# MM32_BLDC.net
KiCad netlist of a schematic drawn in Altium Designer
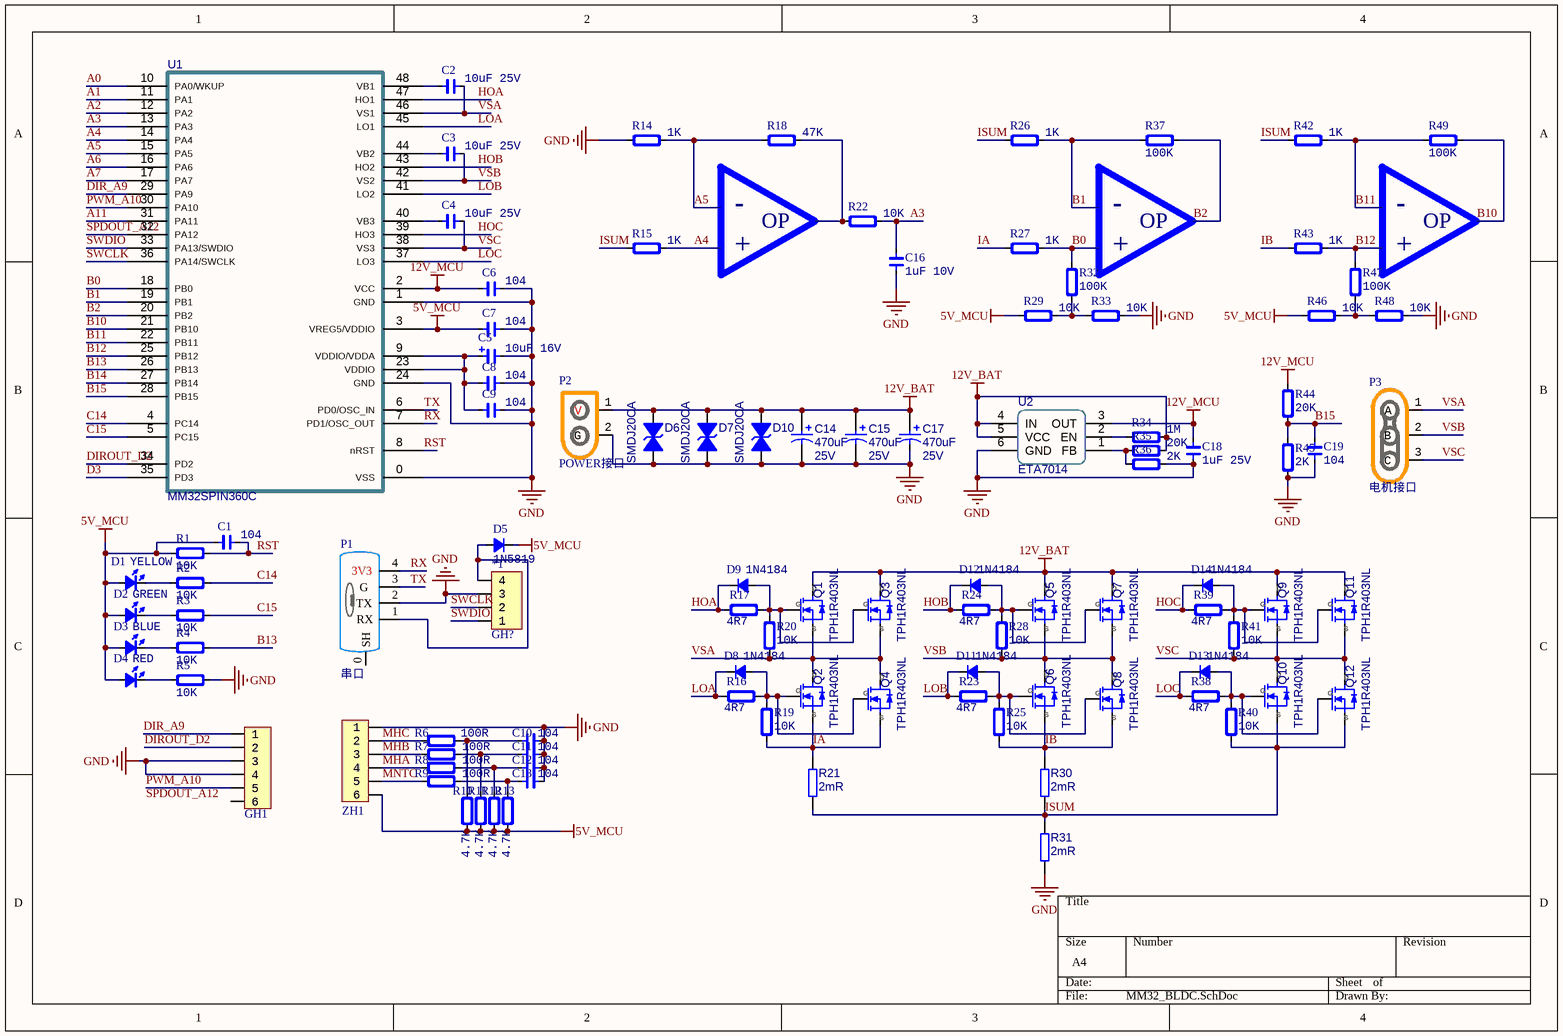
[diagram p0: MM32_BLDC.SchDoc]

(export (version "E")
  (design (tool "Eeschema 10.0.6"))
  (components
    (comp (ref "*1")
      (value "GH?")
      (footprint "MX 1.25-LS-4P")
      (description "MX")
      (libsource (lib "RM") (part "4P接口"))
    )
    (comp (ref "C1")
      (value "104")
      (footprint "CAP_0603")
      (description "Capacitor")
      (libsource (lib "") (part "Cap_0603_1"))
    )
    (comp (ref "C2")
      (value "10uF 25V")
      (footprint "CAP_0603")
      (description "Capacitor")
      (libsource (lib "") (part "Cap_0603_1"))
    )
    (comp (ref "C3")
      (value "10uF 25V")
      (footprint "CAP_0603")
      (description "Capacitor")
      (libsource (lib "") (part "Cap_0603_1"))
    )
    (comp (ref "C4")
      (value "10uF 25V")
      (footprint "CAP_0603")
      (description "Capacitor")
      (libsource (lib "") (part "Cap_0603_1"))
    )
    (comp (ref "C5")
      (value "10uF 16V")
      (footprint "CAP_TAN_A1206")
      (description "Capacitor Tantalum")
      (libsource (lib "KitSprout") (part "Cap_Tan_1206"))
    )
    (comp (ref "C6")
      (value "104")
      (footprint "CAP_0603")
      (description "Capacitor")
      (libsource (lib "") (part "Cap_0603_1"))
    )
    (comp (ref "C7")
      (value "104")
      (footprint "CAP_0603")
      (description "Capacitor")
      (libsource (lib "") (part "Cap_0603_1"))
    )
    (comp (ref "C8")
      (value "104")
      (footprint "CAP_0603")
      (description "Capacitor")
      (libsource (lib "") (part "Cap_0603_1"))
    )
    (comp (ref "C9")
      (value "104")
      (footprint "CAP_0603")
      (description "Capacitor")
      (libsource (lib "") (part "Cap_0603_1"))
    )
    (comp (ref "C10")
      (value "104")
      (footprint "CAP_0603")
      (description "Capacitor")
      (libsource (lib "KitSprout") (part "Cap_0603"))
    )
    (comp (ref "C11")
      (value "104")
      (footprint "CAP_0603")
      (description "Capacitor")
      (libsource (lib "KitSprout") (part "Cap_0603"))
    )
    (comp (ref "C12")
      (value "104")
      (footprint "CAP_0603")
      (description "Capacitor")
      (libsource (lib "KitSprout") (part "Cap_0603"))
    )
    (comp (ref "C13")
      (value "104")
      (footprint "CAP_0603")
      (description "Capacitor")
      (libsource (lib "KitSprout") (part "Cap_0603"))
    )
    (comp (ref "C14")
      (value "470uF")
      (footprint "CAPPR3.5-8X12")
      (description "Polarized Capacitor (Radial)")
      (fields
        (field (name "VOLTAGE") "25V")
        (field (name "Comment") "470uF 25V")
        (field (name "PUBLISHER") "Altium Limited")
      )
      (libsource (lib "灵动SPIN360C 无刷驱动V1.6 集成封装库") (part "Cap-Elect"))
    )
    (comp (ref "C15")
      (value "470uF")
      (footprint "CAPPR3.5-8X12")
      (description "Polarized Capacitor (Radial)")
      (fields
        (field (name "VOLTAGE") "25V")
        (field (name "Comment") "470uF 25V")
        (field (name "PUBLISHER") "Altium Limited")
      )
      (libsource (lib "灵动SPIN360C 无刷驱动V1.6 集成封装库") (part "Cap-Elect"))
    )
    (comp (ref "C16")
      (value "1uF 10V")
      (footprint "CAP_0603")
      (description "Capacitor")
      (libsource (lib "") (part "Cap_0603_2"))
    )
    (comp (ref "C17")
      (value "470uF")
      (footprint "CAPPR3.5-8X12")
      (description "Polarized Capacitor (Radial)")
      (fields
        (field (name "VOLTAGE") "25V")
        (field (name "Comment") "470uF 25V")
        (field (name "PUBLISHER") "Altium Limited")
      )
      (libsource (lib "灵动SPIN360C 无刷驱动V1.6 集成封装库") (part "Cap-Elect"))
    )
    (comp (ref "C18")
      (value "1uF 25V")
      (footprint "CAP_0603")
      (description "Capacitor")
      (libsource (lib "") (part "Cap_0603_2"))
    )
    (comp (ref "C19")
      (value "104")
      (footprint "CAP_0603")
      (description "Capacitor")
      (libsource (lib "") (part "Cap_0603_2"))
    )
    (comp (ref "D1")
      (value "YELLOW")
      (footprint "LED_0603_RED")
      (description "LED")
      (libsource (lib "KitSprout") (part "LED_0603"))
    )
    (comp (ref "D2")
      (value "GREEN")
      (footprint "LED_0603_RED")
      (description "LED")
      (libsource (lib "KitSprout") (part "LED_0603"))
    )
    (comp (ref "D3")
      (value "BLUE")
      (footprint "LED_0603_RED")
      (description "LED")
      (libsource (lib "KitSprout") (part "LED_0603"))
    )
    (comp (ref "D4")
      (value "RED")
      (footprint "LED_0603_RED")
      (description "LED")
      (libsource (lib "KitSprout") (part "LED_0603"))
    )
    (comp (ref "D5")
      (value "1N5819")
      (footprint "SOD-123")
      (description "Diode")
      (libsource (lib "KitSprout") (part "Diode_SOD123"))
    )
    (comp (ref "D6")
      (value "SMDJ20CA")
      (footprint "SMC[DO-214AB]")
      (description "TRANSIENT VOLTAGE  SUPPRESSOR DIODE")
      (fields (field (name "PUBLISHER") "Altium Limited"))
      (libsource (lib "灵动SPIN360C 无刷驱动V1.6 集成封装库") (part "Diode TVS Bi-Dir"))
    )
    (comp (ref "D7")
      (value "SMDJ20CA")
      (footprint "SMC[DO-214AB]")
      (description "TRANSIENT VOLTAGE  SUPPRESSOR DIODE")
      (fields (field (name "PUBLISHER") "Altium Limited"))
      (libsource (lib "灵动SPIN360C 无刷驱动V1.6 集成封装库") (part "Diode TVS Bi-Dir"))
    )
    (comp (ref "D8")
      (value "1N4184")
      (footprint "SOD-323")
      (description "Diode")
      (libsource (lib "KitSprout") (part "Diode_SOD323"))
    )
    (comp (ref "D9")
      (value "1N4184")
      (footprint "SOD-323")
      (description "Diode")
      (libsource (lib "KitSprout") (part "Diode_SOD323"))
    )
    (comp (ref "D10")
      (value "SMDJ20CA")
      (footprint "SMC[DO-214AB]")
      (description "TRANSIENT VOLTAGE  SUPPRESSOR DIODE")
      (fields (field (name "PUBLISHER") "Altium Limited"))
      (libsource (lib "灵动SPIN360C 无刷驱动V1.6 集成封装库") (part "Diode TVS Bi-Dir"))
    )
    (comp (ref "D11")
      (value "1N4184")
      (footprint "SOD-323")
      (description "Diode")
      (libsource (lib "KitSprout") (part "Diode_SOD323"))
    )
    (comp (ref "D12")
      (value "1N4184")
      (footprint "SOD-323")
      (description "Diode")
      (libsource (lib "KitSprout") (part "Diode_SOD323"))
    )
    (comp (ref "D13")
      (value "1N4184")
      (footprint "SOD-323")
      (description "Diode")
      (libsource (lib "KitSprout") (part "Diode_SOD323"))
    )
    (comp (ref "D14")
      (value "1N4184")
      (footprint "SOD-323")
      (description "Diode")
      (libsource (lib "KitSprout") (part "Diode_SOD323"))
    )
    (comp (ref "GH1")
      (value "HDR1x6")
      (footprint "MX 1.25-WS-4P")
      (description "Header")
      (libsource (lib "MM32_FOC") (part "HDR1x6_2.54"))
    )
    (comp (ref "P1")
      (value "串口")
      (footprint "GH1.25-LS-4P")
      (description "MX")
      (libsource (lib "RM") (part "串口"))
    )
    (comp (ref "P2")
      (value "POWER接口")
      (footprint "XT30UPB-M")
      (description "POWER")
      (libsource (lib "RM") (part "POWER接口"))
    )
    (comp (ref "P3") (value "电机接口") (footprint "AMASS-MR30-M") (libsource (lib "RM") (part "电机接口")))
    (comp (ref "Q1")
      (value "TPH1R403NL")
      (footprint "DFN5x6")
      (description "东芝 N沟 MOS")
      (libsource (lib "灵动SPIN360C 无刷驱动V1.6 集成封装库") (part "TPH1R403NL"))
    )
    (comp (ref "Q2")
      (value "TPH1R403NL")
      (footprint "DFN5x6")
      (description "东芝 N沟 MOS")
      (libsource (lib "灵动SPIN360C 无刷驱动V1.6 集成封装库") (part "TPH1R403NL"))
    )
    (comp (ref "Q3")
      (value "TPH1R403NL")
      (footprint "DFN5x6")
      (description "东芝 N沟 MOS")
      (libsource (lib "灵动SPIN360C 无刷驱动V1.6 集成封装库") (part "TPH1R403NL"))
    )
    (comp (ref "Q4")
      (value "TPH1R403NL")
      (footprint "DFN5x6")
      (description "东芝 N沟 MOS")
      (libsource (lib "灵动SPIN360C 无刷驱动V1.6 集成封装库") (part "TPH1R403NL"))
    )
    (comp (ref "Q5")
      (value "TPH1R403NL")
      (footprint "DFN5x6")
      (description "东芝 N沟 MOS")
      (libsource (lib "灵动SPIN360C 无刷驱动V1.6 集成封装库") (part "TPH1R403NL"))
    )
    (comp (ref "Q6")
      (value "TPH1R403NL")
      (footprint "DFN5x6")
      (description "东芝 N沟 MOS")
      (libsource (lib "灵动SPIN360C 无刷驱动V1.6 集成封装库") (part "TPH1R403NL"))
    )
    (comp (ref "Q7")
      (value "TPH1R403NL")
      (footprint "DFN5x6")
      (description "东芝 N沟 MOS")
      (libsource (lib "灵动SPIN360C 无刷驱动V1.6 集成封装库") (part "TPH1R403NL"))
    )
    (comp (ref "Q8")
      (value "TPH1R403NL")
      (footprint "DFN5x6")
      (description "东芝 N沟 MOS")
      (libsource (lib "灵动SPIN360C 无刷驱动V1.6 集成封装库") (part "TPH1R403NL"))
    )
    (comp (ref "Q9")
      (value "TPH1R403NL")
      (footprint "DFN5x6")
      (description "东芝 N沟 MOS")
      (libsource (lib "灵动SPIN360C 无刷驱动V1.6 集成封装库") (part "TPH1R403NL"))
    )
    (comp (ref "Q10")
      (value "TPH1R403NL")
      (footprint "DFN5x6")
      (description "东芝 N沟 MOS")
      (libsource (lib "灵动SPIN360C 无刷驱动V1.6 集成封装库") (part "TPH1R403NL"))
    )
    (comp (ref "Q11")
      (value "TPH1R403NL")
      (footprint "DFN5x6")
      (description "东芝 N沟 MOS")
      (libsource (lib "灵动SPIN360C 无刷驱动V1.6 集成封装库") (part "TPH1R403NL"))
    )
    (comp (ref "Q12")
      (value "TPH1R403NL")
      (footprint "DFN5x6")
      (description "东芝 N沟 MOS")
      (libsource (lib "灵动SPIN360C 无刷驱动V1.6 集成封装库") (part "TPH1R403NL"))
    )
    (comp (ref "R1")
      (value "10K")
      (footprint "RES_0603")
      (description "Resistor")
      (libsource (lib "KitSprout") (part "Res_0603"))
    )
    (comp (ref "R2")
      (value "10K")
      (footprint "RES_0603")
      (description "Resistor")
      (libsource (lib "KitSprout") (part "Res_0603"))
    )
    (comp (ref "R3")
      (value "10K")
      (footprint "RES_0603")
      (description "Resistor")
      (libsource (lib "KitSprout") (part "Res_0603"))
    )
    (comp (ref "R4")
      (value "10K")
      (footprint "RES_0603")
      (description "Resistor")
      (libsource (lib "KitSprout") (part "Res_0603"))
    )
    (comp (ref "R5")
      (value "10K")
      (footprint "RES_0603")
      (description "Resistor")
      (libsource (lib "KitSprout") (part "Res_0603"))
    )
    (comp (ref "R6")
      (value "100R")
      (footprint "RES_0603")
      (description "Resistor")
      (libsource (lib "KitSprout") (part "Res_0603"))
    )
    (comp (ref "R7")
      (value "100R")
      (footprint "RES_0603")
      (description "Resistor")
      (libsource (lib "KitSprout") (part "Res_0603"))
    )
    (comp (ref "R8")
      (value "100R")
      (footprint "RES_0603")
      (description "Resistor")
      (libsource (lib "KitSprout") (part "Res_0603"))
    )
    (comp (ref "R9")
      (value "100R")
      (footprint "RES_0603")
      (description "Resistor")
      (libsource (lib "KitSprout") (part "Res_0603"))
    )
    (comp (ref "R10")
      (value "4.7K")
      (footprint "RES_0603")
      (description "Resistor")
      (libsource (lib "KitSprout") (part "Res_0603"))
    )
    (comp (ref "R11")
      (value "4.7K")
      (footprint "RES_0603")
      (description "Resistor")
      (libsource (lib "KitSprout") (part "Res_0603"))
    )
    (comp (ref "R12")
      (value "4.7K")
      (footprint "RES_0603")
      (description "Resistor")
      (libsource (lib "KitSprout") (part "Res_0603"))
    )
    (comp (ref "R13")
      (value "4.7K")
      (footprint "RES_0603")
      (description "Resistor")
      (libsource (lib "KitSprout") (part "Res_0603"))
    )
    (comp (ref "R14")
      (value "1K")
      (footprint "RES_0603")
      (description "Resistor")
      (libsource (lib "KitSprout") (part "Res_0603"))
    )
    (comp (ref "R15")
      (value "1K")
      (footprint "RES_0603")
      (description "Resistor")
      (libsource (lib "KitSprout") (part "Res_0603"))
    )
    (comp (ref "R16")
      (value "4R7")
      (footprint "RES_0603")
      (description "Resistor")
      (libsource (lib "KitSprout") (part "Res_0603"))
    )
    (comp (ref "R17")
      (value "4R7")
      (footprint "RES_0603")
      (description "Resistor")
      (libsource (lib "KitSprout") (part "Res_0603"))
    )
    (comp (ref "R18")
      (value "47K")
      (footprint "RES_0603")
      (description "Resistor")
      (libsource (lib "KitSprout") (part "Res_0603"))
    )
    (comp (ref "R19")
      (value "10K")
      (footprint "RES_0603")
      (description "Resistor")
      (libsource (lib "KitSprout") (part "Res_0603"))
    )
    (comp (ref "R20")
      (value "10K")
      (footprint "RES_0603")
      (description "Resistor")
      (libsource (lib "KitSprout") (part "Res_0603"))
    )
    (comp (ref "R21")
      (value "2mR")
      (footprint "RESC6332[2512]S")
      (description "贴片电阻")
      (fields (field (name "TOLERANCE") "±1%") (field (name "Comment") "2mR ±1%"))
      (libsource (lib "灵动SPIN360C 无刷驱动V1.6 集成封装库") (part "Res-Chip_11"))
    )
    (comp (ref "R22")
      (value "10K")
      (footprint "RES_0603")
      (description "Resistor")
      (libsource (lib "KitSprout") (part "Res_0603"))
    )
    (comp (ref "R23")
      (value "4R7")
      (footprint "RES_0603")
      (description "Resistor")
      (libsource (lib "KitSprout") (part "Res_0603"))
    )
    (comp (ref "R24")
      (value "4R7")
      (footprint "RES_0603")
      (description "Resistor")
      (libsource (lib "KitSprout") (part "Res_0603"))
    )
    (comp (ref "R25")
      (value "10K")
      (footprint "RES_0603")
      (description "Resistor")
      (libsource (lib "KitSprout") (part "Res_0603"))
    )
    (comp (ref "R26")
      (value "1K")
      (footprint "RES_0603")
      (description "Resistor")
      (libsource (lib "KitSprout") (part "Res_0603"))
    )
    (comp (ref "R27")
      (value "1K")
      (footprint "RES_0603")
      (description "Resistor")
      (libsource (lib "KitSprout") (part "Res_0603"))
    )
    (comp (ref "R28")
      (value "10K")
      (footprint "RES_0603")
      (description "Resistor")
      (libsource (lib "KitSprout") (part "Res_0603"))
    )
    (comp (ref "R29")
      (value "10K")
      (footprint "RES_0603")
      (description "Resistor")
      (libsource (lib "KitSprout") (part "Res_0603"))
    )
    (comp (ref "R30")
      (value "2mR")
      (footprint "RESC6332[2512]S")
      (description "贴片电阻")
      (fields (field (name "TOLERANCE") "±1%") (field (name "Comment") "2mR ±1%"))
      (libsource (lib "灵动SPIN360C 无刷驱动V1.6 集成封装库") (part "Res-Chip_11"))
    )
    (comp (ref "R31")
      (value "2mR")
      (footprint "RESC6332[2512]S")
      (description "贴片电阻")
      (fields (field (name "TOLERANCE") "±1%") (field (name "Comment") "2mR ±1%"))
      (libsource (lib "灵动SPIN360C 无刷驱动V1.6 集成封装库") (part "Res-Chip_11"))
    )
    (comp (ref "R32")
      (value "100K")
      (footprint "RES_0603")
      (description "Resistor")
      (libsource (lib "KitSprout") (part "Res_0603"))
    )
    (comp (ref "R33")
      (value "10K")
      (footprint "RES_0603")
      (description "Resistor")
      (libsource (lib "KitSprout") (part "Res_0603"))
    )
    (comp (ref "R34")
      (value "1M")
      (footprint "RES_0603")
      (description "Resistor")
      (libsource (lib "KitSprout") (part "Res_0603"))
    )
    (comp (ref "R35")
      (value "20K")
      (footprint "RES_0603")
      (description "Resistor")
      (libsource (lib "KitSprout") (part "Res_0603"))
    )
    (comp (ref "R36")
      (value "2K")
      (footprint "RES_0603")
      (description "Resistor")
      (libsource (lib "KitSprout") (part "Res_0603"))
    )
    (comp (ref "R37")
      (value "100K")
      (footprint "RES_0603")
      (description "Resistor")
      (libsource (lib "KitSprout") (part "Res_0603"))
    )
    (comp (ref "R38")
      (value "4R7")
      (footprint "RES_0603")
      (description "Resistor")
      (libsource (lib "KitSprout") (part "Res_0603"))
    )
    (comp (ref "R39")
      (value "4R7")
      (footprint "RES_0603")
      (description "Resistor")
      (libsource (lib "KitSprout") (part "Res_0603"))
    )
    (comp (ref "R40")
      (value "10K")
      (footprint "RES_0603")
      (description "Resistor")
      (libsource (lib "KitSprout") (part "Res_0603"))
    )
    (comp (ref "R41")
      (value "10K")
      (footprint "RES_0603")
      (description "Resistor")
      (libsource (lib "KitSprout") (part "Res_0603"))
    )
    (comp (ref "R42")
      (value "1K")
      (footprint "RES_0603")
      (description "Resistor")
      (libsource (lib "KitSprout") (part "Res_0603"))
    )
    (comp (ref "R43")
      (value "1K")
      (footprint "RES_0603")
      (description "Resistor")
      (libsource (lib "KitSprout") (part "Res_0603"))
    )
    (comp (ref "R44")
      (value "20K")
      (footprint "RES_0603")
      (description "Resistor")
      (libsource (lib "KitSprout") (part "Res_0603"))
    )
    (comp (ref "R45")
      (value "2K")
      (footprint "RES_0603")
      (description "Resistor")
      (libsource (lib "KitSprout") (part "Res_0603"))
    )
    (comp (ref "R46")
      (value "10K")
      (footprint "RES_0603")
      (description "Resistor")
      (libsource (lib "KitSprout") (part "Res_0603"))
    )
    (comp (ref "R47")
      (value "100K")
      (footprint "RES_0603")
      (description "Resistor")
      (libsource (lib "KitSprout") (part "Res_0603"))
    )
    (comp (ref "R48")
      (value "10K")
      (footprint "RES_0603")
      (description "Resistor")
      (libsource (lib "KitSprout") (part "Res_0603"))
    )
    (comp (ref "R49")
      (value "100K")
      (footprint "RES_0603")
      (description "Resistor")
      (libsource (lib "KitSprout") (part "Res_0603"))
    )
    (comp (ref "U1")
      (value "MM32SPIN360C")
      (footprint "QFN48-6x6")
      (fields (field (name "PUBLISHER") "Altium Limited"))
      (libsource (lib "灵动SPIN360C 无刷驱动V1.6 集成封装库") (part "MM32SPIN360C"))
    )
    (comp (ref "U2")
      (value "ETA7014")
      (footprint "SOT-23-6")
      (description "ETA7014 OVP芯片")
      (libsource (lib "灵动SPIN360C 无刷驱动V1.6 集成封装库") (part "ETA7014"))
    )
    (comp (ref "ZH1")
      (value "MX1.25_6P")
      (footprint "ZH1.5-WF-6P")
      (description "MX")
      (libsource (lib "KitSprout") (part "MX1.25_6P"))
    )
  )
  (nets
    (net (code "1") (name "/A0") (class "Default")
      (node (ref "U1") (pin "10") (pinfunction "PA0/WKUP_10") (pintype "passive"))
    )
    (net (code "2") (name "/A1") (class "Default")
      (node (ref "U1") (pin "11") (pinfunction "PA1_11") (pintype "passive"))
    )
    (net (code "3") (name "/A2") (class "Default")
      (node (ref "U1") (pin "12") (pinfunction "PA2_12") (pintype "passive"))
    )
    (net (code "4") (name "/A3") (class "Default")
      (node (ref "C16") (pin "2") (pinfunction "2_2") (pintype "passive"))
      (node (ref "R22") (pin "1") (pinfunction "1_1") (pintype "passive"))
      (node (ref "U1") (pin "13") (pinfunction "PA3_13") (pintype "passive"))
    )
    (net (code "5") (name "/A4") (class "Default")
      (node (ref "R15") (pin "1") (pinfunction "1_1") (pintype "passive"))
      (node (ref "U1") (pin "14") (pinfunction "PA4_14") (pintype "passive"))
    )
    (net (code "6") (name "/A5") (class "Default")
      (node (ref "R14") (pin "1") (pinfunction "1_1") (pintype "passive"))
      (node (ref "R18") (pin "2") (pinfunction "2_2") (pintype "passive"))
      (node (ref "U1") (pin "15") (pinfunction "PA5_15") (pintype "passive"))
    )
    (net (code "7") (name "/A6") (class "Default")
      (node (ref "U1") (pin "16") (pinfunction "PA6_16") (pintype "passive"))
    )
    (net (code "8") (name "/A7") (class "Default")
      (node (ref "U1") (pin "17") (pinfunction "PA7_17") (pintype "passive"))
    )
    (net (code "9") (name "/A11") (class "Default")
      (node (ref "U1") (pin "31") (pinfunction "PA11_31") (pintype "passive"))
    )
    (net (code "10") (name "/B0") (class "Default")
      (node (ref "R27") (pin "1") (pinfunction "1_1") (pintype "passive"))
      (node (ref "R32") (pin "1") (pinfunction "1_1") (pintype "passive"))
      (node (ref "U1") (pin "18") (pinfunction "PB0_18") (pintype "passive"))
    )
    (net (code "11") (name "/B1") (class "Default")
      (node (ref "R26") (pin "1") (pinfunction "1_1") (pintype "passive"))
      (node (ref "R37") (pin "1") (pinfunction "1_1") (pintype "passive"))
      (node (ref "U1") (pin "19") (pinfunction "PB1_19") (pintype "passive"))
    )
    (net (code "12") (name "/B2") (class "Default")
      (node (ref "R37") (pin "2") (pinfunction "2_2") (pintype "passive"))
      (node (ref "U1") (pin "20") (pinfunction "PB2_20") (pintype "passive"))
    )
    (net (code "13") (name "/B10") (class "Default")
      (node (ref "R49") (pin "2") (pinfunction "2_2") (pintype "passive"))
      (node (ref "U1") (pin "21") (pinfunction "PB10_21") (pintype "passive"))
    )
    (net (code "14") (name "/B11") (class "Default")
      (node (ref "R42") (pin "1") (pinfunction "1_1") (pintype "passive"))
      (node (ref "R49") (pin "1") (pinfunction "1_1") (pintype "passive"))
      (node (ref "U1") (pin "22") (pinfunction "PB11_22") (pintype "passive"))
    )
    (net (code "15") (name "/B12") (class "Default")
      (node (ref "R43") (pin "1") (pinfunction "1_1") (pintype "passive"))
      (node (ref "R47") (pin "1") (pinfunction "1_1") (pintype "passive"))
      (node (ref "U1") (pin "25") (pinfunction "PB12_25") (pintype "passive"))
    )
    (net (code "16") (name "/B13") (class "Default")
      (node (ref "R4") (pin "2") (pinfunction "2_2") (pintype "passive"))
      (node (ref "U1") (pin "26") (pinfunction "PB13_26") (pintype "passive"))
    )
    (net (code "17") (name "/B14") (class "Default")
      (node (ref "U1") (pin "27") (pinfunction "PB14_27") (pintype "passive"))
    )
    (net (code "18") (name "/B15") (class "Default")
      (node (ref "C19") (pin "2") (pinfunction "2_2") (pintype "passive"))
      (node (ref "R44") (pin "2") (pinfunction "2_2") (pintype "passive"))
      (node (ref "R45") (pin "1") (pinfunction "1_1") (pintype "passive"))
      (node (ref "U1") (pin "28") (pinfunction "PB15_28") (pintype "passive"))
    )
    (net (code "19") (name "/C14") (class "Default")
      (node (ref "R2") (pin "2") (pinfunction "2_2") (pintype "passive"))
      (node (ref "U1") (pin "4") (pinfunction "PC14_4") (pintype "passive"))
    )
    (net (code "20") (name "/C15") (class "Default")
      (node (ref "R3") (pin "2") (pinfunction "2_2") (pintype "passive"))
      (node (ref "U1") (pin "5") (pinfunction "PC15_5") (pintype "passive"))
    )
    (net (code "21") (name "/D3") (class "Default")
      (node (ref "U1") (pin "35") (pinfunction "PD3_35") (pintype "passive"))
    )
    (net (code "22") (name "/DIROUT_D2") (class "Default")
      (node (ref "GH1") (pin "2") (pinfunction "2_2") (pintype "passive"))
      (node (ref "U1") (pin "34") (pinfunction "PD2_34") (pintype "passive"))
    )
    (net (code "23") (name "/DIR_A9") (class "Default")
      (node (ref "GH1") (pin "1") (pinfunction "1_1") (pintype "passive"))
      (node (ref "U1") (pin "29") (pinfunction "PA9_29") (pintype "passive"))
    )
    (net (code "24") (name "/HOA") (class "Default")
      (node (ref "D9") (pin "2") (pinfunction "K_2") (pintype "passive"))
      (node (ref "R17") (pin "2") (pinfunction "2_2") (pintype "passive"))
      (node (ref "U1") (pin "47") (pinfunction "HO1_47") (pintype "passive"))
    )
    (net (code "25") (name "/HOB") (class "Default")
      (node (ref "D12") (pin "2") (pinfunction "K_2") (pintype "passive"))
      (node (ref "R24") (pin "2") (pinfunction "2_2") (pintype "passive"))
      (node (ref "U1") (pin "43") (pinfunction "HO2_43") (pintype "passive"))
    )
    (net (code "26") (name "/HOC") (class "Default")
      (node (ref "D14") (pin "2") (pinfunction "K_2") (pintype "passive"))
      (node (ref "R39") (pin "2") (pinfunction "2_2") (pintype "passive"))
      (node (ref "U1") (pin "39") (pinfunction "HO3_39") (pintype "passive"))
    )
    (net (code "27") (name "/IA") (class "Default")
      (node (ref "Q2") (pin "3") (pinfunction "S_3") (pintype "passive"))
      (node (ref "Q4") (pin "3") (pinfunction "S_3") (pintype "passive"))
      (node (ref "R19") (pin "2") (pinfunction "2_2") (pintype "passive"))
      (node (ref "R21") (pin "2") (pinfunction "2_2") (pintype "passive"))
      (node (ref "R27") (pin "2") (pinfunction "2_2") (pintype "passive"))
    )
    (net (code "28") (name "/IB") (class "Default")
      (node (ref "Q6") (pin "3") (pinfunction "S_3") (pintype "passive"))
      (node (ref "Q8") (pin "3") (pinfunction "S_3") (pintype "passive"))
      (node (ref "R25") (pin "2") (pinfunction "2_2") (pintype "passive"))
      (node (ref "R30") (pin "2") (pinfunction "2_2") (pintype "passive"))
      (node (ref "R43") (pin "2") (pinfunction "2_2") (pintype "passive"))
    )
    (net (code "29") (name "/ISUM") (class "Default")
      (node (ref "Q10") (pin "3") (pinfunction "S_3") (pintype "passive"))
      (node (ref "Q12") (pin "3") (pinfunction "S_3") (pintype "passive"))
      (node (ref "R15") (pin "2") (pinfunction "2_2") (pintype "passive"))
      (node (ref "R21") (pin "1") (pinfunction "1_1") (pintype "passive"))
      (node (ref "R26") (pin "2") (pinfunction "2_2") (pintype "passive"))
      (node (ref "R30") (pin "1") (pinfunction "1_1") (pintype "passive"))
      (node (ref "R31") (pin "2") (pinfunction "2_2") (pintype "passive"))
      (node (ref "R40") (pin "2") (pinfunction "2_2") (pintype "passive"))
      (node (ref "R42") (pin "2") (pinfunction "2_2") (pintype "passive"))
    )
    (net (code "30") (name "/LOA") (class "Default")
      (node (ref "D8") (pin "2") (pinfunction "K_2") (pintype "passive"))
      (node (ref "R16") (pin "2") (pinfunction "2_2") (pintype "passive"))
      (node (ref "U1") (pin "45") (pinfunction "LO1_45") (pintype "passive"))
    )
    (net (code "31") (name "/LOB") (class "Default")
      (node (ref "D11") (pin "2") (pinfunction "K_2") (pintype "passive"))
      (node (ref "R23") (pin "2") (pinfunction "2_2") (pintype "passive"))
      (node (ref "U1") (pin "41") (pinfunction "LO2_41") (pintype "passive"))
    )
    (net (code "32") (name "/LOC") (class "Default")
      (node (ref "D13") (pin "2") (pinfunction "K_2") (pintype "passive"))
      (node (ref "R38") (pin "2") (pinfunction "2_2") (pintype "passive"))
      (node (ref "U1") (pin "37") (pinfunction "LO3_37") (pintype "passive"))
    )
    (net (code "33") (name "/MHA") (class "Default")
      (node (ref "R8") (pin "1") (pinfunction "1_1") (pintype "passive"))
      (node (ref "ZH1") (pin "4") (pinfunction "4_4") (pintype "passive"))
    )
    (net (code "34") (name "/MHB") (class "Default")
      (node (ref "R7") (pin "1") (pinfunction "1_1") (pintype "passive"))
      (node (ref "ZH1") (pin "3") (pinfunction "3_3") (pintype "passive"))
    )
    (net (code "35") (name "/MHC") (class "Default")
      (node (ref "R6") (pin "1") (pinfunction "1_1") (pintype "passive"))
      (node (ref "ZH1") (pin "2") (pinfunction "2_2") (pintype "passive"))
    )
    (net (code "36") (name "/MNTC") (class "Default")
      (node (ref "R9") (pin "1") (pinfunction "1_1") (pintype "passive"))
      (node (ref "ZH1") (pin "5") (pinfunction "5_5") (pintype "passive"))
    )
    (net (code "37") (name "/PWM_A10") (class "Default")
      (node (ref "GH1") (pin "5") (pinfunction "5_5") (pintype "passive"))
      (node (ref "U1") (pin "30") (pinfunction "PA10_30") (pintype "passive"))
    )
    (net (code "38") (name "/RST") (class "Default")
      (node (ref "C1") (pin "2") (pinfunction "2_2") (pintype "passive"))
      (node (ref "R1") (pin "2") (pinfunction "2_2") (pintype "passive"))
      (node (ref "U1") (pin "8") (pinfunction "nRST_8") (pintype "passive"))
    )
    (net (code "39") (name "/RX") (class "Default")
      (node (ref "P1") (pin "4") (pinfunction "3V3_4") (pintype "passive"))
      (node (ref "U1") (pin "7") (pinfunction "PD1/OSC_OUT_7") (pintype "passive"))
    )
    (net (code "40") (name "/SPDOUT_A12") (class "Default")
      (node (ref "U1") (pin "32") (pinfunction "PA12_32") (pintype "passive"))
    )
    (net (code "41") (name "/SWCLK") (class "Default")
      (node (ref "*1") (pin "2") (pinfunction "2_2") (pintype "passive"))
      (node (ref "U1") (pin "36") (pinfunction "PA14/SWCLK_36") (pintype "passive"))
    )
    (net (code "42") (name "/SWDIO") (class "Default")
      (node (ref "*1") (pin "1") (pinfunction "1_1") (pintype "passive"))
      (node (ref "U1") (pin "33") (pinfunction "PA13/SWDIO_33") (pintype "passive"))
    )
    (net (code "43") (name "/TX") (class "Default")
      (node (ref "P1") (pin "3") (pinfunction "G_3") (pintype "passive"))
      (node (ref "U1") (pin "6") (pinfunction "PD0/OSC_IN_6") (pintype "passive"))
    )
    (net (code "44") (name "/VSA") (class "Default")
      (node (ref "C2") (pin "2") (pinfunction "2_2") (pintype "passive"))
      (node (ref "P3") (pin "1") (pinfunction "A_1") (pintype "passive"))
      (node (ref "Q1") (pin "3") (pinfunction "S_3") (pintype "passive"))
      (node (ref "Q2") (pin "1") (pinfunction "D_1") (pintype "passive"))
      (node (ref "Q3") (pin "3") (pinfunction "S_3") (pintype "passive"))
      (node (ref "Q4") (pin "1") (pinfunction "D_1") (pintype "passive"))
      (node (ref "R20") (pin "2") (pinfunction "2_2") (pintype "passive"))
      (node (ref "U1") (pin "46") (pinfunction "VS1_46") (pintype "passive"))
    )
    (net (code "45") (name "/VSB") (class "Default")
      (node (ref "C3") (pin "2") (pinfunction "2_2") (pintype "passive"))
      (node (ref "P3") (pin "2") (pinfunction "B_2") (pintype "passive"))
      (node (ref "Q5") (pin "3") (pinfunction "S_3") (pintype "passive"))
      (node (ref "Q6") (pin "1") (pinfunction "D_1") (pintype "passive"))
      (node (ref "Q7") (pin "3") (pinfunction "S_3") (pintype "passive"))
      (node (ref "Q8") (pin "1") (pinfunction "D_1") (pintype "passive"))
      (node (ref "R28") (pin "2") (pinfunction "2_2") (pintype "passive"))
      (node (ref "U1") (pin "42") (pinfunction "VS2_42") (pintype "passive"))
    )
    (net (code "46") (name "/VSC") (class "Default")
      (node (ref "C4") (pin "2") (pinfunction "2_2") (pintype "passive"))
      (node (ref "P3") (pin "3") (pinfunction "C_3") (pintype "passive"))
      (node (ref "Q10") (pin "1") (pinfunction "D_1") (pintype "passive"))
      (node (ref "Q11") (pin "3") (pinfunction "S_3") (pintype "passive"))
      (node (ref "Q12") (pin "1") (pinfunction "D_1") (pintype "passive"))
      (node (ref "Q9") (pin "3") (pinfunction "S_3") (pintype "passive"))
      (node (ref "R41") (pin "2") (pinfunction "2_2") (pintype "passive"))
      (node (ref "U1") (pin "38") (pinfunction "VS3_38") (pintype "passive"))
    )
    (net (code "47") (name "5V_MCU") (class "Default")
      (node (ref "C1") (pin "1") (pinfunction "1_1") (pintype "passive"))
      (node (ref "C7") (pin "1") (pinfunction "1_1") (pintype "passive"))
      (node (ref "D1") (pin "1") (pinfunction "A_1") (pintype "passive"))
      (node (ref "D2") (pin "1") (pinfunction "A_1") (pintype "passive"))
      (node (ref "D3") (pin "1") (pinfunction "A_1") (pintype "passive"))
      (node (ref "D4") (pin "1") (pinfunction "A_1") (pintype "passive"))
      (node (ref "D5") (pin "2") (pinfunction "K_2") (pintype "passive"))
      (node (ref "R1") (pin "1") (pinfunction "1_1") (pintype "passive"))
      (node (ref "R10") (pin "2") (pinfunction "2_2") (pintype "passive"))
      (node (ref "R11") (pin "2") (pinfunction "2_2") (pintype "passive"))
      (node (ref "R12") (pin "2") (pinfunction "2_2") (pintype "passive"))
      (node (ref "R13") (pin "2") (pinfunction "2_2") (pintype "passive"))
      (node (ref "R29") (pin "2") (pinfunction "2_2") (pintype "passive"))
      (node (ref "R46") (pin "2") (pinfunction "2_2") (pintype "passive"))
      (node (ref "U1") (pin "3") (pinfunction "VREG5/VDDIO_3") (pintype "passive"))
      (node (ref "ZH1") (pin "6") (pinfunction "6_6") (pintype "passive"))
    )
    (net (code "48") (name "12V_BAT") (class "Default")
      (node (ref "C14") (pin "1") (pinfunction "1_1") (pintype "passive"))
      (node (ref "C15") (pin "1") (pinfunction "1_1") (pintype "passive"))
      (node (ref "C17") (pin "1") (pinfunction "1_1") (pintype "passive"))
      (node (ref "D10") (pin "K") (pinfunction "K_K") (pintype "passive"))
      (node (ref "D6") (pin "K") (pinfunction "K_K") (pintype "passive"))
      (node (ref "D7") (pin "K") (pinfunction "K_K") (pintype "passive"))
      (node (ref "P2") (pin "1") (pinfunction "V_1") (pintype "passive"))
      (node (ref "Q1") (pin "1") (pinfunction "D_1") (pintype "passive"))
      (node (ref "Q11") (pin "1") (pinfunction "D_1") (pintype "passive"))
      (node (ref "Q3") (pin "1") (pinfunction "D_1") (pintype "passive"))
      (node (ref "Q5") (pin "1") (pinfunction "D_1") (pintype "passive"))
      (node (ref "Q7") (pin "1") (pinfunction "D_1") (pintype "passive"))
      (node (ref "Q9") (pin "1") (pinfunction "D_1") (pintype "passive"))
      (node (ref "R34") (pin "1") (pinfunction "1_1") (pintype "passive"))
      (node (ref "R35") (pin "1") (pinfunction "1_1") (pintype "passive"))
      (node (ref "U2") (pin "4") (pinfunction "IN_4") (pintype "passive"))
      (node (ref "U2") (pin "5") (pinfunction "VCC_5") (pintype "passive"))
    )
    (net (code "49") (name "12V_MCU") (class "Default")
      (node (ref "C18") (pin "2") (pinfunction "2_2") (pintype "passive"))
      (node (ref "C6") (pin "1") (pinfunction "1_1") (pintype "passive"))
      (node (ref "R44") (pin "1") (pinfunction "1_1") (pintype "passive"))
      (node (ref "U1") (pin "2") (pinfunction "VCC_2") (pintype "passive"))
      (node (ref "U2") (pin "3") (pinfunction "OUT_3") (pintype "passive"))
    )
    (net (code "50") (name "GND") (class "Default")
      (node (ref "*1") (pin "3") (pinfunction "3_3") (pintype "passive"))
      (node (ref "C10") (pin "1") (pinfunction "1_1") (pintype "passive"))
      (node (ref "C11") (pin "1") (pinfunction "1_1") (pintype "passive"))
      (node (ref "C12") (pin "1") (pinfunction "1_1") (pintype "passive"))
      (node (ref "C13") (pin "1") (pinfunction "1_1") (pintype "passive"))
      (node (ref "C14") (pin "2") (pinfunction "2_2") (pintype "passive"))
      (node (ref "C15") (pin "2") (pinfunction "2_2") (pintype "passive"))
      (node (ref "C16") (pin "1") (pinfunction "1_1") (pintype "passive"))
      (node (ref "C17") (pin "2") (pinfunction "2_2") (pintype "passive"))
      (node (ref "C18") (pin "1") (pinfunction "1_1") (pintype "passive"))
      (node (ref "C19") (pin "1") (pinfunction "1_1") (pintype "passive"))
      (node (ref "C5") (pin "2") (pinfunction "2_2") (pintype "passive"))
      (node (ref "C6") (pin "2") (pinfunction "2_2") (pintype "passive"))
      (node (ref "C7") (pin "2") (pinfunction "2_2") (pintype "passive"))
      (node (ref "C8") (pin "2") (pinfunction "2_2") (pintype "passive"))
      (node (ref "C9") (pin "2") (pinfunction "2_2") (pintype "passive"))
      (node (ref "D10") (pin "A") (pinfunction "A_A") (pintype "passive"))
      (node (ref "D6") (pin "A") (pinfunction "A_A") (pintype "passive"))
      (node (ref "D7") (pin "A") (pinfunction "A_A") (pintype "passive"))
      (node (ref "GH1") (pin "3") (pinfunction "3_3") (pintype "passive"))
      (node (ref "GH1") (pin "4") (pinfunction "4_4") (pintype "passive"))
      (node (ref "P1") (pin "2") (pinfunction "TX_2") (pintype "passive"))
      (node (ref "P2") (pin "2") (pinfunction "G_2") (pintype "passive"))
      (node (ref "R14") (pin "2") (pinfunction "2_2") (pintype "passive"))
      (node (ref "R31") (pin "1") (pinfunction "1_1") (pintype "passive"))
      (node (ref "R33") (pin "1") (pinfunction "1_1") (pintype "passive"))
      (node (ref "R36") (pin "1") (pinfunction "1_1") (pintype "passive"))
      (node (ref "R45") (pin "2") (pinfunction "2_2") (pintype "passive"))
      (node (ref "R48") (pin "1") (pinfunction "1_1") (pintype "passive"))
      (node (ref "R5") (pin "2") (pinfunction "2_2") (pintype "passive"))
      (node (ref "U1") (pin "0") (pinfunction "VSS_0") (pintype "passive"))
      (node (ref "U1") (pin "1") (pinfunction "GND_1") (pintype "passive"))
      (node (ref "U1") (pin "24") (pinfunction "GND_24") (pintype "passive"))
      (node (ref "U2") (pin "6") (pinfunction "GND_6") (pintype "passive"))
      (node (ref "ZH1") (pin "1") (pinfunction "1_1") (pintype "passive"))
    )
    (net (code "51") (name "Net-(C10-Pad2)") (class "Default")
      (node (ref "C10") (pin "2") (pinfunction "2_2") (pintype "passive"))
      (node (ref "R10") (pin "1") (pinfunction "1_1") (pintype "passive"))
      (node (ref "R6") (pin "2") (pinfunction "2_2") (pintype "passive"))
    )
    (net (code "52") (name "Net-(C11-Pad2)") (class "Default")
      (node (ref "C11") (pin "2") (pinfunction "2_2") (pintype "passive"))
      (node (ref "R11") (pin "1") (pinfunction "1_1") (pintype "passive"))
      (node (ref "R7") (pin "2") (pinfunction "2_2") (pintype "passive"))
    )
    (net (code "53") (name "Net-(C12-Pad2)") (class "Default")
      (node (ref "C12") (pin "2") (pinfunction "2_2") (pintype "passive"))
      (node (ref "R12") (pin "1") (pinfunction "1_1") (pintype "passive"))
      (node (ref "R8") (pin "2") (pinfunction "2_2") (pintype "passive"))
    )
    (net (code "54") (name "Net-(C13-Pad2)") (class "Default")
      (node (ref "C13") (pin "2") (pinfunction "2_2") (pintype "passive"))
      (node (ref "R13") (pin "1") (pinfunction "1_1") (pintype "passive"))
      (node (ref "R9") (pin "2") (pinfunction "2_2") (pintype "passive"))
    )
    (net (code "55") (name "Net-(D1-K)") (class "Default")
      (node (ref "D1") (pin "2") (pinfunction "K_2") (pintype "passive"))
      (node (ref "R2") (pin "1") (pinfunction "1_1") (pintype "passive"))
    )
    (net (code "56") (name "Net-(D2-K)") (class "Default")
      (node (ref "D2") (pin "2") (pinfunction "K_2") (pintype "passive"))
      (node (ref "R3") (pin "1") (pinfunction "1_1") (pintype "passive"))
    )
    (net (code "57") (name "Net-(D3-K)") (class "Default")
      (node (ref "D3") (pin "2") (pinfunction "K_2") (pintype "passive"))
      (node (ref "R4") (pin "1") (pinfunction "1_1") (pintype "passive"))
    )
    (net (code "58") (name "Net-(D4-K)") (class "Default")
      (node (ref "D4") (pin "2") (pinfunction "K_2") (pintype "passive"))
      (node (ref "R5") (pin "1") (pinfunction "1_1") (pintype "passive"))
    )
    (net (code "59") (name "Net-(D5-A)") (class "Default")
      (node (ref "*1") (pin "4") (pinfunction "4_4") (pintype "passive"))
      (node (ref "D5") (pin "1") (pinfunction "A_1") (pintype "passive"))
      (node (ref "P1") (pin "1") (pinfunction "RX_1") (pintype "passive"))
    )
    (net (code "60") (name "Net-(D8-A)") (class "Default")
      (node (ref "D8") (pin "1") (pinfunction "A_1") (pintype "passive"))
      (node (ref "Q2") (pin "2") (pinfunction "G_2") (pintype "passive"))
      (node (ref "Q4") (pin "2") (pinfunction "G_2") (pintype "passive"))
      (node (ref "R16") (pin "1") (pinfunction "1_1") (pintype "passive"))
      (node (ref "R19") (pin "1") (pinfunction "1_1") (pintype "passive"))
    )
    (net (code "61") (name "Net-(D9-A)") (class "Default")
      (node (ref "D9") (pin "1") (pinfunction "A_1") (pintype "passive"))
      (node (ref "Q1") (pin "2") (pinfunction "G_2") (pintype "passive"))
      (node (ref "Q3") (pin "2") (pinfunction "G_2") (pintype "passive"))
      (node (ref "R17") (pin "1") (pinfunction "1_1") (pintype "passive"))
      (node (ref "R20") (pin "1") (pinfunction "1_1") (pintype "passive"))
    )
    (net (code "62") (name "Net-(D11-A)") (class "Default")
      (node (ref "D11") (pin "1") (pinfunction "A_1") (pintype "passive"))
      (node (ref "Q6") (pin "2") (pinfunction "G_2") (pintype "passive"))
      (node (ref "Q8") (pin "2") (pinfunction "G_2") (pintype "passive"))
      (node (ref "R23") (pin "1") (pinfunction "1_1") (pintype "passive"))
      (node (ref "R25") (pin "1") (pinfunction "1_1") (pintype "passive"))
    )
    (net (code "63") (name "Net-(D12-A)") (class "Default")
      (node (ref "D12") (pin "1") (pinfunction "A_1") (pintype "passive"))
      (node (ref "Q5") (pin "2") (pinfunction "G_2") (pintype "passive"))
      (node (ref "Q7") (pin "2") (pinfunction "G_2") (pintype "passive"))
      (node (ref "R24") (pin "1") (pinfunction "1_1") (pintype "passive"))
      (node (ref "R28") (pin "1") (pinfunction "1_1") (pintype "passive"))
    )
    (net (code "64") (name "Net-(D13-A)") (class "Default")
      (node (ref "D13") (pin "1") (pinfunction "A_1") (pintype "passive"))
      (node (ref "Q10") (pin "2") (pinfunction "G_2") (pintype "passive"))
      (node (ref "Q12") (pin "2") (pinfunction "G_2") (pintype "passive"))
      (node (ref "R38") (pin "1") (pinfunction "1_1") (pintype "passive"))
      (node (ref "R40") (pin "1") (pinfunction "1_1") (pintype "passive"))
    )
    (net (code "65") (name "Net-(D14-A)") (class "Default")
      (node (ref "D14") (pin "1") (pinfunction "A_1") (pintype "passive"))
      (node (ref "Q11") (pin "2") (pinfunction "G_2") (pintype "passive"))
      (node (ref "Q9") (pin "2") (pinfunction "G_2") (pintype "passive"))
      (node (ref "R39") (pin "1") (pinfunction "1_1") (pintype "passive"))
      (node (ref "R41") (pin "1") (pinfunction "1_1") (pintype "passive"))
    )
    (net (code "66") (name "Net-(R18-Pad1)") (class "Default")
      (node (ref "R18") (pin "1") (pinfunction "1_1") (pintype "passive"))
      (node (ref "R22") (pin "2") (pinfunction "2_2") (pintype "passive"))
    )
    (net (code "67") (name "Net-(R29-Pad1)") (class "Default")
      (node (ref "R29") (pin "1") (pinfunction "1_1") (pintype "passive"))
      (node (ref "R32") (pin "2") (pinfunction "2_2") (pintype "passive"))
      (node (ref "R33") (pin "2") (pinfunction "2_2") (pintype "passive"))
    )
    (net (code "68") (name "Net-(R46-Pad1)") (class "Default")
      (node (ref "R46") (pin "1") (pinfunction "1_1") (pintype "passive"))
      (node (ref "R47") (pin "2") (pinfunction "2_2") (pintype "passive"))
      (node (ref "R48") (pin "2") (pinfunction "2_2") (pintype "passive"))
    )
    (net (code "69") (name "Net-(U1-VB1)") (class "Default")
      (node (ref "C2") (pin "1") (pinfunction "1_1") (pintype "passive"))
      (node (ref "U1") (pin "48") (pinfunction "VB1_48") (pintype "passive"))
    )
    (net (code "70") (name "Net-(U1-VB2)") (class "Default")
      (node (ref "C3") (pin "1") (pinfunction "1_1") (pintype "passive"))
      (node (ref "U1") (pin "44") (pinfunction "VB2_44") (pintype "passive"))
    )
    (net (code "71") (name "Net-(U1-VB3)") (class "Default")
      (node (ref "C4") (pin "1") (pinfunction "1_1") (pintype "passive"))
      (node (ref "U1") (pin "40") (pinfunction "VB3_40") (pintype "passive"))
    )
    (net (code "72") (name "Net-(U1-VDDIO)") (class "Default")
      (node (ref "C5") (pin "1") (pinfunction "1_1") (pintype "passive"))
      (node (ref "C8") (pin "1") (pinfunction "1_1") (pintype "passive"))
      (node (ref "C9") (pin "1") (pinfunction "1_1") (pintype "passive"))
      (node (ref "U1") (pin "23") (pinfunction "VDDIO_23") (pintype "passive"))
      (node (ref "U1") (pin "9") (pinfunction "VDDIO/VDDA_9") (pintype "passive"))
    )
    (net (code "73") (name "Net-(U2-EN)") (class "Default")
      (node (ref "R34") (pin "2") (pinfunction "2_2") (pintype "passive"))
      (node (ref "U2") (pin "2") (pinfunction "EN_2") (pintype "passive"))
    )
    (net (code "74") (name "Net-(U2-FB)") (class "Default")
      (node (ref "R35") (pin "2") (pinfunction "2_2") (pintype "passive"))
      (node (ref "R36") (pin "2") (pinfunction "2_2") (pintype "passive"))
      (node (ref "U2") (pin "1") (pinfunction "FB_1") (pintype "passive"))
    )
    (net (code "75") (name "unconnected-(GH1-Pad6)") (class "Default")
      (node (ref "GH1") (pin "6") (pinfunction "6_6") (pintype "passive"))
    )
    (net (code "76") (name "unconnected-(P1-SH-Pad0)") (class "Default")
      (node (ref "P1") (pin "0") (pinfunction "SH_0") (pintype "passive"))
    )
    (net (code "77") (name "unconnected-(ZH1-Pad0)") (class "Default")
      (node (ref "ZH1") (pin "0") (pinfunction "0_0") (pintype "passive"))
    )
  )
)
